# Fishbot_receiver.net
KiCad netlist of a schematic drawn in EAGLE
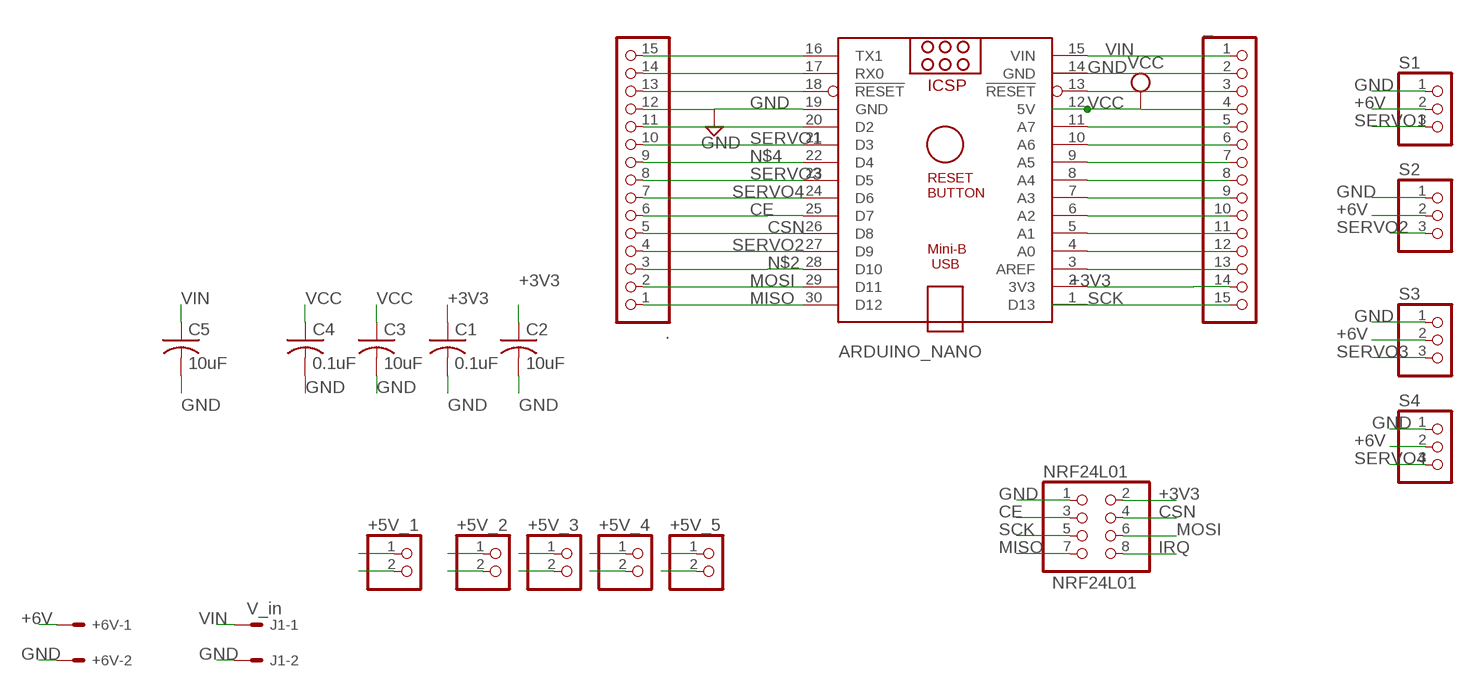
[diagram p0: schematic, sheet 1]

(export (version "E")
  (design (tool "Eeschema 10.0.6"))
  (components
    (comp (ref "+5V_1")
      (value "PINHD-1X2")
      (footprint "eagle-import:1X02")
      (libsource (lib "eagle-import") (part "PINHD-1X2"))
    )
    (comp (ref "+5V_2")
      (value "PINHD-1X2")
      (footprint "eagle-import:1X02")
      (libsource (lib "eagle-import") (part "PINHD-1X2"))
    )
    (comp (ref "+5V_3")
      (value "PINHD-1X2")
      (footprint "eagle-import:1X02")
      (libsource (lib "eagle-import") (part "PINHD-1X2"))
    )
    (comp (ref "+5V_4")
      (value "PINHD-1X2")
      (footprint "eagle-import:1X02")
      (libsource (lib "eagle-import") (part "PINHD-1X2"))
    )
    (comp (ref "+5V_5")
      (value "PINHD-1X2")
      (footprint "eagle-import:1X02")
      (libsource (lib "eagle-import") (part "PINHD-1X2"))
    )
    (comp (ref "+6V")
      (value "22-27-2021-02")
      (footprint "eagle-import:6410-02")
      (fields (field (name "MF") "MOLEX"))
      (libsource (lib "eagle-import") (part "22-?-0227-2021"))
    )
    (comp (ref ".")
      (value "PINHD-1X15")
      (footprint "eagle-import:1X15")
      (libsource (lib "eagle-import") (part "PINHD-1X15"))
    )
    (comp (ref "ARDUINO_NANO")
      (value "ARDUINO_NANO")
      (footprint "eagle-import:ARDUINO_NANO")
      (libsource (lib "eagle-import") (part "ARDUINO_NANO"))
    )
    (comp (ref "C1")
      (value "0.1uF")
      (footprint "eagle-import:C1206")
      (libsource (lib "eagle-import") (part "C-USC1206"))
    )
    (comp (ref "C2")
      (value "10uF")
      (footprint "eagle-import:C1206")
      (libsource (lib "eagle-import") (part "C-USC1206"))
    )
    (comp (ref "C3")
      (value "10uF")
      (footprint "eagle-import:C1206")
      (libsource (lib "eagle-import") (part "C-USC1206"))
    )
    (comp (ref "C4")
      (value "0.1uF")
      (footprint "eagle-import:C1206")
      (libsource (lib "eagle-import") (part "C-USC1206"))
    )
    (comp (ref "C5")
      (value "10uF")
      (footprint "eagle-import:C1206")
      (libsource (lib "eagle-import") (part "C-USC1206"))
    )
    (comp (ref "J1")
      (value "V_in")
      (footprint "eagle-import:6410-02")
      (fields (field (name "MF") "MOLEX"))
      (libsource (lib "eagle-import") (part "22-?-0227-2021"))
    )
    (comp (ref "NRF24L01")
      (value "PINHD-2X4")
      (footprint "eagle-import:2X04")
      (libsource (lib "eagle-import") (part "PINHD-2X4"))
    )
    (comp (ref "S1")
      (value "PINHD-1X3")
      (footprint "eagle-import:1X03")
      (libsource (lib "eagle-import") (part "PINHD-1X3"))
    )
    (comp (ref "S2")
      (value "PINHD-1X3")
      (footprint "eagle-import:1X03")
      (libsource (lib "eagle-import") (part "PINHD-1X3"))
    )
    (comp (ref "S3")
      (value "PINHD-1X3")
      (footprint "eagle-import:1X03")
      (libsource (lib "eagle-import") (part "PINHD-1X3"))
    )
    (comp (ref "S4")
      (value "PINHD-1X3")
      (footprint "eagle-import:1X03")
      (libsource (lib "eagle-import") (part "PINHD-1X3"))
    )
    (comp (ref "_")
      (value "PINHD-1X15")
      (footprint "eagle-import:1X15")
      (libsource (lib "eagle-import") (part "PINHD-1X15"))
    )
  )
  (nets
    (net (code "1") (name "/+3V3") (class "Default")
      (node (ref "ARDUINO_NANO") (pin "2") (pinfunction "3V3_2") (pintype "output"))
      (node (ref "C1") (pin "1") (pinfunction "1_1") (pintype "passive"))
      (node (ref "C2") (pin "1") (pinfunction "1_1") (pintype "passive"))
      (node (ref "NRF24L01") (pin "2") (pinfunction "2_2") (pintype "passive"))
      (node (ref "_") (pin "14") (pinfunction "14_14") (pintype "passive"))
    )
    (net (code "2") (name "/+6V") (class "Default")
      (node (ref "+6V") (pin "1") (pinfunction "S_1") (pintype "passive"))
      (node (ref "S1") (pin "2") (pinfunction "2_2") (pintype "passive"))
      (node (ref "S2") (pin "2") (pinfunction "2_2") (pintype "passive"))
      (node (ref "S3") (pin "2") (pinfunction "2_2") (pintype "passive"))
      (node (ref "S4") (pin "2") (pinfunction "2_2") (pintype "passive"))
    )
    (net (code "3") (name "/CE") (class "Default")
      (node (ref ".") (pin "6") (pinfunction "6_6") (pintype "passive"))
      (node (ref "ARDUINO_NANO") (pin "25") (pinfunction "D7_25") (pintype "bidirectional"))
      (node (ref "NRF24L01") (pin "3") (pinfunction "3_3") (pintype "passive"))
    )
    (net (code "4") (name "/CSN") (class "Default")
      (node (ref ".") (pin "5") (pinfunction "5_5") (pintype "passive"))
      (node (ref "ARDUINO_NANO") (pin "26") (pinfunction "D8_26") (pintype "bidirectional"))
      (node (ref "NRF24L01") (pin "4") (pinfunction "4_4") (pintype "passive"))
    )
    (net (code "5") (name "/IRQ") (class "Default")
      (node (ref "NRF24L01") (pin "8") (pinfunction "8_8") (pintype "passive"))
    )
    (net (code "6") (name "/MISO") (class "Default")
      (node (ref ".") (pin "1") (pinfunction "1_1") (pintype "passive"))
      (node (ref "ARDUINO_NANO") (pin "30") (pinfunction "D12_30") (pintype "bidirectional"))
      (node (ref "NRF24L01") (pin "7") (pinfunction "7_7") (pintype "passive"))
    )
    (net (code "7") (name "/MOSI") (class "Default")
      (node (ref ".") (pin "2") (pinfunction "2_2") (pintype "passive"))
      (node (ref "ARDUINO_NANO") (pin "29") (pinfunction "D11_29") (pintype "bidirectional"))
      (node (ref "NRF24L01") (pin "6") (pinfunction "6_6") (pintype "passive"))
    )
    (net (code "8") (name "/N$2") (class "Default")
      (node (ref ".") (pin "3") (pinfunction "3_3") (pintype "passive"))
      (node (ref "ARDUINO_NANO") (pin "28") (pinfunction "D10_28") (pintype "bidirectional"))
    )
    (net (code "9") (name "/N$4") (class "Default")
      (node (ref ".") (pin "9") (pinfunction "9_9") (pintype "passive"))
      (node (ref "ARDUINO_NANO") (pin "22") (pinfunction "D4_22") (pintype "bidirectional"))
    )
    (net (code "10") (name "/SCK") (class "Default")
      (node (ref "ARDUINO_NANO") (pin "1") (pinfunction "D13_1") (pintype "bidirectional"))
      (node (ref "NRF24L01") (pin "5") (pinfunction "5_5") (pintype "passive"))
      (node (ref "_") (pin "15") (pinfunction "15_15") (pintype "passive"))
    )
    (net (code "11") (name "/SERVO1") (class "Default")
      (node (ref ".") (pin "10") (pinfunction "10_10") (pintype "passive"))
      (node (ref "ARDUINO_NANO") (pin "21") (pinfunction "D3_21") (pintype "bidirectional"))
      (node (ref "S1") (pin "3") (pinfunction "3_3") (pintype "passive"))
    )
    (net (code "12") (name "/SERVO2") (class "Default")
      (node (ref ".") (pin "4") (pinfunction "4_4") (pintype "passive"))
      (node (ref "ARDUINO_NANO") (pin "27") (pinfunction "D9_27") (pintype "bidirectional"))
      (node (ref "S2") (pin "3") (pinfunction "3_3") (pintype "passive"))
    )
    (net (code "13") (name "/SERVO3") (class "Default")
      (node (ref ".") (pin "8") (pinfunction "8_8") (pintype "passive"))
      (node (ref "ARDUINO_NANO") (pin "23") (pinfunction "D5_23") (pintype "bidirectional"))
      (node (ref "S3") (pin "3") (pinfunction "3_3") (pintype "passive"))
    )
    (net (code "14") (name "/SERVO4") (class "Default")
      (node (ref ".") (pin "7") (pinfunction "7_7") (pintype "passive"))
      (node (ref "ARDUINO_NANO") (pin "24") (pinfunction "D6_24") (pintype "bidirectional"))
      (node (ref "S4") (pin "3") (pinfunction "3_3") (pintype "passive"))
    )
    (net (code "15") (name "/VIN") (class "Default")
      (node (ref "ARDUINO_NANO") (pin "15") (pinfunction "VIN_15") (pintype "power_in"))
      (node (ref "C5") (pin "1") (pinfunction "1_1") (pintype "passive"))
      (node (ref "J1") (pin "1") (pinfunction "S_1") (pintype "passive"))
      (node (ref "_") (pin "1") (pinfunction "1_1") (pintype "passive"))
    )
    (net (code "16") (name "GND") (class "Default")
      (node (ref "+5V_1") (pin "2") (pinfunction "2_2") (pintype "passive"))
      (node (ref "+5V_2") (pin "2") (pinfunction "2_2") (pintype "passive"))
      (node (ref "+5V_3") (pin "2") (pinfunction "2_2") (pintype "passive"))
      (node (ref "+5V_4") (pin "2") (pinfunction "2_2") (pintype "passive"))
      (node (ref "+5V_5") (pin "2") (pinfunction "2_2") (pintype "passive"))
      (node (ref "+6V") (pin "2") (pinfunction "S_2") (pintype "passive"))
      (node (ref ".") (pin "12") (pinfunction "12_12") (pintype "passive"))
      (node (ref "ARDUINO_NANO") (pin "14") (pinfunction "GND_14") (pintype "power_in"))
      (node (ref "ARDUINO_NANO") (pin "19") (pinfunction "GND_19") (pintype "power_in"))
      (node (ref "C1") (pin "2") (pinfunction "2_2") (pintype "passive"))
      (node (ref "C2") (pin "2") (pinfunction "2_2") (pintype "passive"))
      (node (ref "C3") (pin "2") (pinfunction "2_2") (pintype "passive"))
      (node (ref "C4") (pin "2") (pinfunction "2_2") (pintype "passive"))
      (node (ref "C5") (pin "2") (pinfunction "2_2") (pintype "passive"))
      (node (ref "J1") (pin "2") (pinfunction "S_2") (pintype "passive"))
      (node (ref "NRF24L01") (pin "1") (pinfunction "1_1") (pintype "passive"))
      (node (ref "S1") (pin "1") (pinfunction "1_1") (pintype "passive"))
      (node (ref "S2") (pin "1") (pinfunction "1_1") (pintype "passive"))
      (node (ref "S3") (pin "1") (pinfunction "1_1") (pintype "passive"))
      (node (ref "S4") (pin "1") (pinfunction "1_1") (pintype "passive"))
      (node (ref "_") (pin "2") (pinfunction "2_2") (pintype "passive"))
    )
    (net (code "17") (name "Net-(.-Pad13)") (class "Default")
      (node (ref ".") (pin "13") (pinfunction "13_13") (pintype "passive"))
      (node (ref "ARDUINO_NANO") (pin "18") (pinfunction "~{RESET}_18") (pintype "input"))
    )
    (net (code "18") (name "Net-(ARDUINO_NANO-A0)") (class "Default")
      (node (ref "ARDUINO_NANO") (pin "4") (pinfunction "A0_4") (pintype "bidirectional"))
      (node (ref "_") (pin "12") (pinfunction "12_12") (pintype "passive"))
    )
    (net (code "19") (name "Net-(ARDUINO_NANO-A1)") (class "Default")
      (node (ref "ARDUINO_NANO") (pin "5") (pinfunction "A1_5") (pintype "bidirectional"))
      (node (ref "_") (pin "11") (pinfunction "11_11") (pintype "passive"))
    )
    (net (code "20") (name "Net-(ARDUINO_NANO-A2)") (class "Default")
      (node (ref "ARDUINO_NANO") (pin "6") (pinfunction "A2_6") (pintype "bidirectional"))
      (node (ref "_") (pin "10") (pinfunction "10_10") (pintype "passive"))
    )
    (net (code "21") (name "Net-(ARDUINO_NANO-A3)") (class "Default")
      (node (ref "ARDUINO_NANO") (pin "7") (pinfunction "A3_7") (pintype "bidirectional"))
      (node (ref "_") (pin "9") (pinfunction "9_9") (pintype "passive"))
    )
    (net (code "22") (name "Net-(ARDUINO_NANO-A4)") (class "Default")
      (node (ref "ARDUINO_NANO") (pin "8") (pinfunction "A4_8") (pintype "bidirectional"))
      (node (ref "_") (pin "8") (pinfunction "8_8") (pintype "passive"))
    )
    (net (code "23") (name "Net-(ARDUINO_NANO-A5)") (class "Default")
      (node (ref "ARDUINO_NANO") (pin "9") (pinfunction "A5_9") (pintype "bidirectional"))
      (node (ref "_") (pin "7") (pinfunction "7_7") (pintype "passive"))
    )
    (net (code "24") (name "Net-(ARDUINO_NANO-A6)") (class "Default")
      (node (ref "ARDUINO_NANO") (pin "10") (pinfunction "A6_10") (pintype "bidirectional"))
      (node (ref "_") (pin "6") (pinfunction "6_6") (pintype "passive"))
    )
    (net (code "25") (name "Net-(ARDUINO_NANO-A7)") (class "Default")
      (node (ref "ARDUINO_NANO") (pin "11") (pinfunction "A7_11") (pintype "bidirectional"))
      (node (ref "_") (pin "5") (pinfunction "5_5") (pintype "passive"))
    )
    (net (code "26") (name "Net-(ARDUINO_NANO-AREF)") (class "Default")
      (node (ref "ARDUINO_NANO") (pin "3") (pinfunction "AREF_3") (pintype "input"))
      (node (ref "_") (pin "13") (pinfunction "13_13") (pintype "passive"))
    )
    (net (code "27") (name "Net-(ARDUINO_NANO-D2)") (class "Default")
      (node (ref ".") (pin "11") (pinfunction "11_11") (pintype "passive"))
      (node (ref "ARDUINO_NANO") (pin "20") (pinfunction "D2_20") (pintype "bidirectional"))
    )
    (net (code "28") (name "Net-(ARDUINO_NANO-RX0)") (class "Default")
      (node (ref ".") (pin "14") (pinfunction "14_14") (pintype "passive"))
      (node (ref "ARDUINO_NANO") (pin "17") (pinfunction "RX0_17") (pintype "bidirectional"))
    )
    (net (code "29") (name "Net-(ARDUINO_NANO-TX1)") (class "Default")
      (node (ref ".") (pin "15") (pinfunction "15_15") (pintype "passive"))
      (node (ref "ARDUINO_NANO") (pin "16") (pinfunction "TX1_16") (pintype "bidirectional"))
    )
    (net (code "30") (name "Net-(ARDUINO_NANO-~{RESET}-Pad13)") (class "Default")
      (node (ref "ARDUINO_NANO") (pin "13") (pinfunction "~{RESET}_13") (pintype "input"))
      (node (ref "_") (pin "3") (pinfunction "3_3") (pintype "passive"))
    )
    (net (code "31") (name "VCC") (class "Default")
      (node (ref "+5V_1") (pin "1") (pinfunction "1_1") (pintype "passive"))
      (node (ref "+5V_2") (pin "1") (pinfunction "1_1") (pintype "passive"))
      (node (ref "+5V_3") (pin "1") (pinfunction "1_1") (pintype "passive"))
      (node (ref "+5V_4") (pin "1") (pinfunction "1_1") (pintype "passive"))
      (node (ref "+5V_5") (pin "1") (pinfunction "1_1") (pintype "passive"))
      (node (ref "ARDUINO_NANO") (pin "12") (pinfunction "5V_12") (pintype "power_in"))
      (node (ref "C3") (pin "1") (pinfunction "1_1") (pintype "passive"))
      (node (ref "C4") (pin "1") (pinfunction "1_1") (pintype "passive"))
      (node (ref "_") (pin "4") (pinfunction "4_4") (pintype "passive"))
    )
  )
)
